# master_taylor.net
KiCad netlist of a schematic drawn in EAGLE
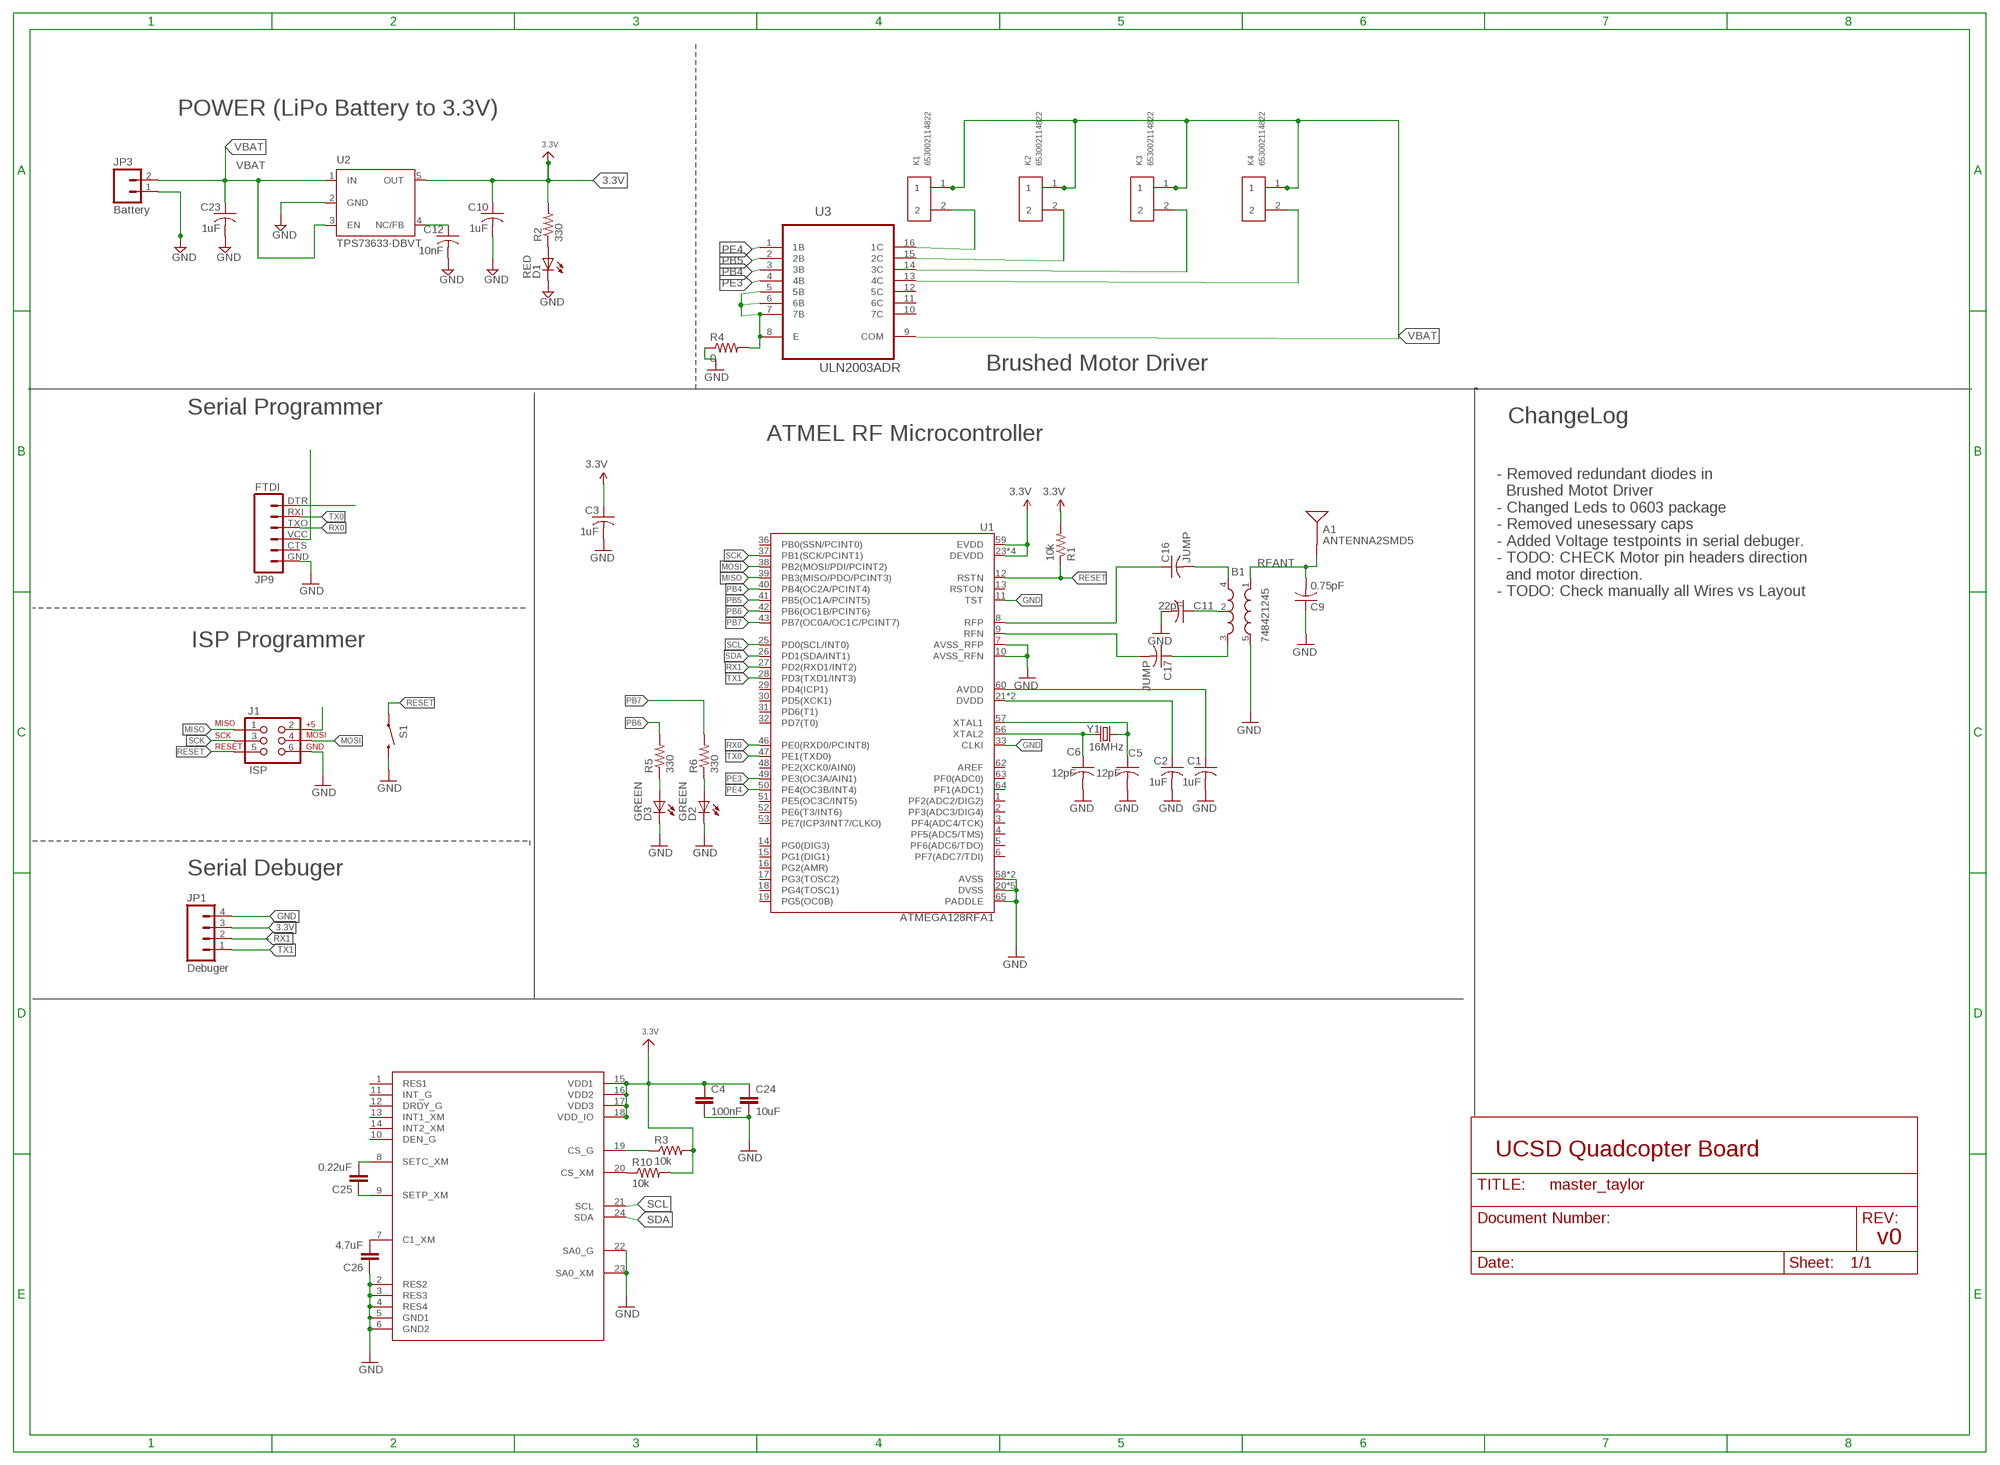
[diagram p0: schematic, sheet 1]

(export (version "E")
  (design (tool "Eeschema 10.0.6"))
  (components
    (comp (ref "A1")
      (value "ANTENNA2SMD5")
      (footprint "eagle-import:ANTENNA-CHIP5")
      (libsource (lib "eagle-import") (part "ANTENNA2SMD5"))
    )
    (comp (ref "B1")
      (value "748421245")
      (footprint "eagle-import:BALUN")
      (libsource (lib "eagle-import") (part "BALUN0805"))
    )
    (comp (ref "C1")
      (value "1uF")
      (footprint "eagle-import:C0805")
      (libsource (lib "eagle-import") (part "C-USC0805"))
    )
    (comp (ref "C2")
      (value "1uF")
      (footprint "eagle-import:C0805")
      (libsource (lib "eagle-import") (part "C-USC0805"))
    )
    (comp (ref "C3")
      (value "1uF")
      (footprint "eagle-import:C0805")
      (libsource (lib "eagle-import") (part "C-USC0805"))
    )
    (comp (ref "C4")
      (value "100nF")
      (footprint "eagle-import:0805")
      (libsource (lib "eagle-import") (part "CAP0805"))
    )
    (comp (ref "C5")
      (value "12pF")
      (footprint "eagle-import:C0805")
      (libsource (lib "eagle-import") (part "C-USC0805"))
    )
    (comp (ref "C6")
      (value "12pF")
      (footprint "eagle-import:C0805")
      (libsource (lib "eagle-import") (part "C-USC0805"))
    )
    (comp (ref "C9")
      (value "0.75pF")
      (footprint "eagle-import:C0805")
      (libsource (lib "eagle-import") (part "C-USC0805"))
    )
    (comp (ref "C10")
      (value "1uF")
      (footprint "eagle-import:C0805")
      (libsource (lib "eagle-import") (part "C-USC0805"))
    )
    (comp (ref "C11")
      (value "22pF")
      (footprint "eagle-import:C0805")
      (libsource (lib "eagle-import") (part "C-USC0805"))
    )
    (comp (ref "C12")
      (value "10nF")
      (footprint "eagle-import:C0805")
      (libsource (lib "eagle-import") (part "C-USC0805"))
    )
    (comp (ref "C16")
      (value "JUMP")
      (footprint "eagle-import:C0805")
      (libsource (lib "eagle-import") (part "C-USC0805"))
    )
    (comp (ref "C17")
      (value "JUMP")
      (footprint "eagle-import:C0805")
      (libsource (lib "eagle-import") (part "C-USC0805"))
    )
    (comp (ref "C23")
      (value "1uF")
      (footprint "eagle-import:C0805")
      (libsource (lib "eagle-import") (part "C-USC0805"))
    )
    (comp (ref "C24")
      (value "10uF")
      (footprint "eagle-import:0805")
      (libsource (lib "eagle-import") (part "CAP0805"))
    )
    (comp (ref "C25")
      (value "0.22uF")
      (footprint "eagle-import:0805")
      (libsource (lib "eagle-import") (part "CAP0805"))
    )
    (comp (ref "C26")
      (value "4.7uF")
      (footprint "eagle-import:0805")
      (libsource (lib "eagle-import") (part "CAP0805"))
    )
    (comp (ref "D1")
      (value "RED")
      (footprint "eagle-import:CHIPLED_0603")
      (libsource (lib "eagle-import") (part "LEDCHIPLED_0603"))
    )
    (comp (ref "D2")
      (value "GREEN")
      (footprint "eagle-import:CHIPLED_0603")
      (libsource (lib "eagle-import") (part "LEDCHIPLED_0603"))
    )
    (comp (ref "D3")
      (value "GREEN")
      (footprint "eagle-import:CHIPLED_0603")
      (libsource (lib "eagle-import") (part "LEDCHIPLED_0603"))
    )
    (comp (ref "J1")
      (value "ISP")
      (footprint "eagle-import:2X3-NS")
      (libsource (lib "eagle-import") (part "AVR_SPI_PRG_6NS"))
    )
    (comp (ref "JP1")
      (value "Debuger")
      (footprint "eagle-import:1X04")
      (libsource (lib "eagle-import") (part "M04PTH"))
    )
    (comp (ref "JP3")
      (value "Battery")
      (footprint "eagle-import:1X02")
      (libsource (lib "eagle-import") (part "M02PTH"))
    )
    (comp (ref "JP9")
      (value "FTDI")
      (footprint "eagle-import:FTDI_BASIC")
      (libsource (lib "eagle-import") (part "FTDI_BASICPTH"))
    )
    (comp (ref "K1")
      (value "653002114822")
      (footprint "eagle-import:653002114822")
      (libsource (lib "eagle-import") (part "653002114822"))
    )
    (comp (ref "K2")
      (value "653002114822")
      (footprint "eagle-import:653002114822")
      (libsource (lib "eagle-import") (part "653002114822"))
    )
    (comp (ref "K3")
      (value "653002114822")
      (footprint "eagle-import:653002114822")
      (libsource (lib "eagle-import") (part "653002114822"))
    )
    (comp (ref "K4")
      (value "653002114822")
      (footprint "eagle-import:653002114822")
      (libsource (lib "eagle-import") (part "653002114822"))
    )
    (comp (ref "R1")
      (value "10k")
      (footprint "eagle-import:R0805")
      (libsource (lib "eagle-import") (part "R-US_R0805"))
    )
    (comp (ref "R2")
      (value "330")
      (footprint "eagle-import:R0805")
      (libsource (lib "eagle-import") (part "R-US_R0805"))
    )
    (comp (ref "R3")
      (value "10k")
      (footprint "eagle-import:0805")
      (libsource (lib "eagle-import") (part "RESISTOR0805-RES"))
    )
    (comp (ref "R4")
      (value "0")
      (footprint "eagle-import:0805")
      (libsource (lib "eagle-import") (part "RESISTOR0805-RES"))
    )
    (comp (ref "R5")
      (value "330")
      (footprint "eagle-import:R0805")
      (libsource (lib "eagle-import") (part "R-US_R0805"))
    )
    (comp (ref "R6")
      (value "330")
      (footprint "eagle-import:R0805")
      (libsource (lib "eagle-import") (part "R-US_R0805"))
    )
    (comp (ref "R10")
      (value "10k")
      (footprint "eagle-import:0805")
      (libsource (lib "eagle-import") (part "RESISTOR0805-RES"))
    )
    (comp (ref "S1")
      (value "SWITCH-MOMENTARY-2SMD")
      (footprint "eagle-import:TACTILE_SWITCH_SMD")
      (libsource (lib "eagle-import") (part "SWITCH-MOMENTARY-2SMD"))
    )
    (comp (ref "U$1")
      (value "LSM9DS0")
      (footprint "eagle-import:LGA-24")
      (libsource (lib "eagle-import") (part "LSM9DS0"))
    )
    (comp (ref "U1")
      (value "ATMEGA128RFA1")
      (footprint "eagle-import:QFN-64")
      (libsource (lib "eagle-import") (part "ATMEGA128RFA1"))
    )
    (comp (ref "U2")
      (value "TPS73633-DBVT")
      (footprint "eagle-import:SOT23-DBV")
      (libsource (lib "eagle-import") (part "TPS73633-DBVT"))
    )
    (comp (ref "U3")
      (value "ULN2003ADR")
      (footprint "eagle-import:SOIC127P600X175-16N")
      (libsource (lib "eagle-import") (part "ULN2003ADR"))
    )
    (comp (ref "Y1")
      (value "16MHz")
      (footprint "eagle-import:CRYSTAL-SMD-5X3")
      (libsource (lib "eagle-import") (part "CRYSTAL5X3"))
    )
  )
  (nets
    (net (code "1") (name "/RFANT") (class "Default")
      (node (ref "A1") (pin "FEED") (pinfunction "SIGNAL_FEED") (pintype "bidirectional"))
      (node (ref "B1") (pin "1") (pinfunction "IN_1") (pintype "bidirectional"))
      (node (ref "C9") (pin "2") (pinfunction "2_2") (pintype "passive"))
    )
    (net (code "2") (name "3.3V") (class "Default")
      (node (ref "C10") (pin "1") (pinfunction "1_1") (pintype "passive"))
      (node (ref "C24") (pin "1") (pinfunction "1_1") (pintype "passive"))
      (node (ref "C3") (pin "1") (pinfunction "1_1") (pintype "passive"))
      (node (ref "C4") (pin "1") (pinfunction "1_1") (pintype "passive"))
      (node (ref "JP1") (pin "3") (pinfunction "3_3") (pintype "passive"))
      (node (ref "R1") (pin "2") (pinfunction "2_2") (pintype "passive"))
      (node (ref "R10") (pin "2") (pinfunction "2_2") (pintype "passive"))
      (node (ref "R2") (pin "2") (pinfunction "2_2") (pintype "passive"))
      (node (ref "R3") (pin "2") (pinfunction "2_2") (pintype "passive"))
      (node (ref "U$1") (pin "15") (pinfunction "VDD1_15") (pintype "bidirectional"))
      (node (ref "U$1") (pin "16") (pinfunction "VDD2_16") (pintype "bidirectional"))
      (node (ref "U$1") (pin "17") (pinfunction "VDD3_17") (pintype "bidirectional"))
      (node (ref "U$1") (pin "18") (pinfunction "VDD_IO_18") (pintype "bidirectional"))
      (node (ref "U1") (pin "23") (pinfunction "DEVDD_23") (pintype "bidirectional"))
      (node (ref "U1") (pin "34") (pinfunction "DEVDD_34") (pintype "bidirectional"))
      (node (ref "U1") (pin "44") (pinfunction "DEVDD_44") (pintype "bidirectional"))
      (node (ref "U1") (pin "54") (pinfunction "DEVDD_54") (pintype "bidirectional"))
      (node (ref "U1") (pin "59") (pinfunction "EVDD_59") (pintype "bidirectional"))
      (node (ref "U2") (pin "5") (pinfunction "OUT_5") (pintype "passive"))
    )
    (net (code "3") (name "GND") (class "Default")
      (node (ref "B1") (pin "5") (pinfunction "GND_5") (pintype "bidirectional"))
      (node (ref "C1") (pin "2") (pinfunction "2_2") (pintype "passive"))
      (node (ref "C10") (pin "2") (pinfunction "2_2") (pintype "passive"))
      (node (ref "C11") (pin "2") (pinfunction "2_2") (pintype "passive"))
      (node (ref "C12") (pin "2") (pinfunction "2_2") (pintype "passive"))
      (node (ref "C2") (pin "2") (pinfunction "2_2") (pintype "passive"))
      (node (ref "C23") (pin "2") (pinfunction "2_2") (pintype "passive"))
      (node (ref "C24") (pin "2") (pinfunction "2_2") (pintype "passive"))
      (node (ref "C26") (pin "1") (pinfunction "1_1") (pintype "passive"))
      (node (ref "C3") (pin "2") (pinfunction "2_2") (pintype "passive"))
      (node (ref "C4") (pin "2") (pinfunction "2_2") (pintype "passive"))
      (node (ref "C5") (pin "2") (pinfunction "2_2") (pintype "passive"))
      (node (ref "C6") (pin "2") (pinfunction "2_2") (pintype "passive"))
      (node (ref "C9") (pin "1") (pinfunction "1_1") (pintype "passive"))
      (node (ref "D1") (pin "C") (pinfunction "C_C") (pintype "passive"))
      (node (ref "D2") (pin "C") (pinfunction "C_C") (pintype "passive"))
      (node (ref "D3") (pin "C") (pinfunction "C_C") (pintype "passive"))
      (node (ref "J1") (pin "6") (pinfunction "6_6") (pintype "passive"))
      (node (ref "JP1") (pin "4") (pinfunction "4_4") (pintype "passive"))
      (node (ref "JP3") (pin "1") (pinfunction "1_1") (pintype "passive"))
      (node (ref "JP9") (pin "GND") (pinfunction "6_GND") (pintype "passive"))
      (node (ref "R4") (pin "1") (pinfunction "1_1") (pintype "passive"))
      (node (ref "S1") (pin "3") (pinfunction "2_3") (pintype "passive"))
      (node (ref "U$1") (pin "2") (pinfunction "RES2_2") (pintype "bidirectional"))
      (node (ref "U$1") (pin "22") (pinfunction "SA0_G_22") (pintype "bidirectional"))
      (node (ref "U$1") (pin "23") (pinfunction "SA0_XM_23") (pintype "bidirectional"))
      (node (ref "U$1") (pin "3") (pinfunction "RES3_3") (pintype "bidirectional"))
      (node (ref "U$1") (pin "4") (pinfunction "RES4_4") (pintype "bidirectional"))
      (node (ref "U$1") (pin "5") (pinfunction "GND1_5") (pintype "bidirectional"))
      (node (ref "U$1") (pin "6") (pinfunction "GND2_6") (pintype "bidirectional"))
      (node (ref "U1") (pin "10") (pinfunction "AVSS_RFN_10") (pintype "bidirectional"))
      (node (ref "U1") (pin "11") (pinfunction "TST_11") (pintype "bidirectional"))
      (node (ref "U1") (pin "20") (pinfunction "DVSS_20") (pintype "bidirectional"))
      (node (ref "U1") (pin "24") (pinfunction "DVSS_24") (pintype "bidirectional"))
      (node (ref "U1") (pin "33") (pinfunction "CLKI_33") (pintype "bidirectional"))
      (node (ref "U1") (pin "35") (pinfunction "DVSS_35") (pintype "bidirectional"))
      (node (ref "U1") (pin "45") (pinfunction "DVSS_45") (pintype "bidirectional"))
      (node (ref "U1") (pin "55") (pinfunction "DVSS_55") (pintype "bidirectional"))
      (node (ref "U1") (pin "58") (pinfunction "AVSS_58") (pintype "bidirectional"))
      (node (ref "U1") (pin "61") (pinfunction "AVSS_61") (pintype "bidirectional"))
      (node (ref "U1") (pin "65") (pinfunction "PADDLE_65") (pintype "bidirectional"))
      (node (ref "U1") (pin "7") (pinfunction "AVSS_RFP_7") (pintype "bidirectional"))
      (node (ref "U2") (pin "2") (pinfunction "GND_2") (pintype "input"))
    )
    (net (code "4") (name "MISO") (class "Default")
      (node (ref "J1") (pin "1") (pinfunction "1_1") (pintype "passive"))
      (node (ref "U1") (pin "39") (pinfunction "PB3(MISO/PDO/PCINT3)_39") (pintype "bidirectional"))
    )
    (net (code "5") (name "MOSI") (class "Default")
      (node (ref "J1") (pin "4") (pinfunction "4_4") (pintype "passive"))
      (node (ref "U1") (pin "38") (pinfunction "PB2(MOSI/PDI/PCINT2)_38") (pintype "bidirectional"))
    )
    (net (code "6") (name "Net-(B1-GND-Pad2)") (class "Default")
      (node (ref "B1") (pin "2") (pinfunction "GND_2") (pintype "bidirectional"))
      (node (ref "C11") (pin "1") (pinfunction "1_1") (pintype "passive"))
    )
    (net (code "7") (name "Net-(B1-OUT1)") (class "Default")
      (node (ref "B1") (pin "4") (pinfunction "OUT1_4") (pintype "bidirectional"))
      (node (ref "C16") (pin "2") (pinfunction "2_2") (pintype "passive"))
    )
    (net (code "8") (name "Net-(B1-OUT2)") (class "Default")
      (node (ref "B1") (pin "3") (pinfunction "OUT2_3") (pintype "bidirectional"))
      (node (ref "C17") (pin "1") (pinfunction "1_1") (pintype "passive"))
    )
    (net (code "9") (name "Net-(C2-Pad1)") (class "Default")
      (node (ref "C2") (pin "1") (pinfunction "1_1") (pintype "passive"))
      (node (ref "U1") (pin "21") (pinfunction "DVDD_21") (pintype "bidirectional"))
      (node (ref "U1") (pin "22") (pinfunction "DVDD_22") (pintype "bidirectional"))
    )
    (net (code "10") (name "Net-(D1-PadA)") (class "Default")
      (node (ref "D1") (pin "A") (pinfunction "A_A") (pintype "passive"))
      (node (ref "R2") (pin "1") (pinfunction "1_1") (pintype "passive"))
    )
    (net (code "11") (name "Net-(D2-PadA)") (class "Default")
      (node (ref "D2") (pin "A") (pinfunction "A_A") (pintype "passive"))
      (node (ref "R6") (pin "1") (pinfunction "1_1") (pintype "passive"))
    )
    (net (code "12") (name "Net-(D3-PadA)") (class "Default")
      (node (ref "D3") (pin "A") (pinfunction "A_A") (pintype "passive"))
      (node (ref "R5") (pin "1") (pinfunction "1_1") (pintype "passive"))
    )
    (net (code "13") (name "Net-(U$1-C1_XM)") (class "Default")
      (node (ref "C26") (pin "2") (pinfunction "2_2") (pintype "passive"))
      (node (ref "U$1") (pin "7") (pinfunction "C1_XM_7") (pintype "bidirectional"))
    )
    (net (code "14") (name "Net-(U$1-CS_G)") (class "Default")
      (node (ref "R3") (pin "1") (pinfunction "1_1") (pintype "passive"))
      (node (ref "U$1") (pin "19") (pinfunction "CS_G_19") (pintype "bidirectional"))
    )
    (net (code "15") (name "Net-(U$1-CS_XM)") (class "Default")
      (node (ref "R10") (pin "1") (pinfunction "1_1") (pintype "passive"))
      (node (ref "U$1") (pin "20") (pinfunction "CS_XM_20") (pintype "bidirectional"))
    )
    (net (code "16") (name "Net-(U$1-SETC_XM)") (class "Default")
      (node (ref "C25") (pin "2") (pinfunction "2_2") (pintype "passive"))
      (node (ref "U$1") (pin "8") (pinfunction "SETC_XM_8") (pintype "bidirectional"))
    )
    (net (code "17") (name "Net-(U$1-SETP_XM)") (class "Default")
      (node (ref "C25") (pin "1") (pinfunction "1_1") (pintype "passive"))
      (node (ref "U$1") (pin "9") (pinfunction "SETP_XM_9") (pintype "bidirectional"))
    )
    (net (code "18") (name "Net-(U1-AVDD)") (class "Default")
      (node (ref "C1") (pin "1") (pinfunction "1_1") (pintype "passive"))
      (node (ref "U1") (pin "60") (pinfunction "AVDD_60") (pintype "bidirectional"))
    )
    (net (code "19") (name "Net-(U1-RFN)") (class "Default")
      (node (ref "C17") (pin "2") (pinfunction "2_2") (pintype "passive"))
      (node (ref "U1") (pin "9") (pinfunction "RFN_9") (pintype "bidirectional"))
    )
    (net (code "20") (name "Net-(U1-RFP)") (class "Default")
      (node (ref "C16") (pin "1") (pinfunction "1_1") (pintype "passive"))
      (node (ref "U1") (pin "8") (pinfunction "RFP_8") (pintype "bidirectional"))
    )
    (net (code "21") (name "Net-(U1-XTAL1)") (class "Default")
      (node (ref "C5") (pin "1") (pinfunction "1_1") (pintype "passive"))
      (node (ref "U1") (pin "57") (pinfunction "XTAL1_57") (pintype "bidirectional"))
      (node (ref "Y1") (pin "3") (pinfunction "2_3") (pintype "passive"))
    )
    (net (code "22") (name "Net-(U1-XTAL2)") (class "Default")
      (node (ref "C6") (pin "1") (pinfunction "1_1") (pintype "passive"))
      (node (ref "U1") (pin "56") (pinfunction "XTAL2_56") (pintype "bidirectional"))
      (node (ref "Y1") (pin "1") (pinfunction "1_1") (pintype "passive"))
    )
    (net (code "23") (name "Net-(U2-NC{slash}FB)") (class "Default")
      (node (ref "C12") (pin "1") (pinfunction "1_1") (pintype "passive"))
      (node (ref "U2") (pin "4") (pinfunction "NC/FB_4") (pintype "passive"))
    )
    (net (code "24") (name "Net-(U3-1C)") (class "Default")
      (node (ref "K1") (pin "2") (pinfunction "2_2") (pintype "bidirectional"))
      (node (ref "U3") (pin "16") (pinfunction "1C_16") (pintype "output"))
    )
    (net (code "25") (name "Net-(U3-2C)") (class "Default")
      (node (ref "K2") (pin "2") (pinfunction "2_2") (pintype "bidirectional"))
      (node (ref "U3") (pin "15") (pinfunction "2C_15") (pintype "output"))
    )
    (net (code "26") (name "Net-(U3-3C)") (class "Default")
      (node (ref "K3") (pin "2") (pinfunction "2_2") (pintype "bidirectional"))
      (node (ref "U3") (pin "14") (pinfunction "3C_14") (pintype "output"))
    )
    (net (code "27") (name "Net-(U3-4C)") (class "Default")
      (node (ref "K4") (pin "2") (pinfunction "2_2") (pintype "bidirectional"))
      (node (ref "U3") (pin "13") (pinfunction "4C_13") (pintype "output"))
    )
    (net (code "28") (name "Net-(U3-5B)") (class "Default")
      (node (ref "R4") (pin "2") (pinfunction "2_2") (pintype "passive"))
      (node (ref "U3") (pin "5") (pinfunction "5B_5") (pintype "input"))
      (node (ref "U3") (pin "6") (pinfunction "6B_6") (pintype "input"))
      (node (ref "U3") (pin "7") (pinfunction "7B_7") (pintype "input"))
      (node (ref "U3") (pin "8") (pinfunction "E_8") (pintype "input"))
    )
    (net (code "29") (name "PB4") (class "Default")
      (node (ref "U1") (pin "40") (pinfunction "PB4(OC2A/PCINT4)_40") (pintype "bidirectional"))
      (node (ref "U3") (pin "3") (pinfunction "3B_3") (pintype "input"))
    )
    (net (code "30") (name "PB5") (class "Default")
      (node (ref "U1") (pin "41") (pinfunction "PB5(OC1A/PCINT5)_41") (pintype "bidirectional"))
      (node (ref "U3") (pin "2") (pinfunction "2B_2") (pintype "input"))
    )
    (net (code "31") (name "PB6") (class "Default")
      (node (ref "R5") (pin "2") (pinfunction "2_2") (pintype "passive"))
      (node (ref "U1") (pin "42") (pinfunction "PB6(OC1B/PCINT6)_42") (pintype "bidirectional"))
    )
    (net (code "32") (name "PB7") (class "Default")
      (node (ref "R6") (pin "2") (pinfunction "2_2") (pintype "passive"))
      (node (ref "U1") (pin "43") (pinfunction "PB7(OC0A/OC1C/PCINT7)_43") (pintype "bidirectional"))
    )
    (net (code "33") (name "PE3") (class "Default")
      (node (ref "U1") (pin "49") (pinfunction "PE3(OC3A/AIN1)_49") (pintype "bidirectional"))
      (node (ref "U3") (pin "4") (pinfunction "4B_4") (pintype "input"))
    )
    (net (code "34") (name "PE4") (class "Default")
      (node (ref "U1") (pin "50") (pinfunction "PE4(OC3B/INT4)_50") (pintype "bidirectional"))
      (node (ref "U3") (pin "1") (pinfunction "1B_1") (pintype "input"))
    )
    (net (code "35") (name "RESET") (class "Default")
      (node (ref "J1") (pin "5") (pinfunction "5_5") (pintype "passive"))
      (node (ref "R1") (pin "1") (pinfunction "1_1") (pintype "passive"))
      (node (ref "S1") (pin "1") (pinfunction "1_1") (pintype "passive"))
      (node (ref "U1") (pin "12") (pinfunction "RSTN_12") (pintype "bidirectional"))
    )
    (net (code "36") (name "RX0") (class "Default")
      (node (ref "JP9") (pin "TXO") (pinfunction "3_TXO") (pintype "passive"))
      (node (ref "U1") (pin "46") (pinfunction "PE0(RXD0/PCINT8)_46") (pintype "bidirectional"))
    )
    (net (code "37") (name "RX1") (class "Default")
      (node (ref "JP1") (pin "2") (pinfunction "2_2") (pintype "passive"))
      (node (ref "U1") (pin "27") (pinfunction "PD2(RXD1/INT2)_27") (pintype "bidirectional"))
    )
    (net (code "38") (name "SCK") (class "Default")
      (node (ref "J1") (pin "3") (pinfunction "3_3") (pintype "passive"))
      (node (ref "U1") (pin "37") (pinfunction "PB1(SCK/PCINT1)_37") (pintype "bidirectional"))
    )
    (net (code "39") (name "SCL") (class "Default")
      (node (ref "U$1") (pin "21") (pinfunction "SCL_21") (pintype "bidirectional"))
      (node (ref "U1") (pin "25") (pinfunction "PD0(SCL/INT0)_25") (pintype "bidirectional"))
    )
    (net (code "40") (name "SDA") (class "Default")
      (node (ref "U$1") (pin "24") (pinfunction "SDA_24") (pintype "bidirectional"))
      (node (ref "U1") (pin "26") (pinfunction "PD1(SDA/INT1)_26") (pintype "bidirectional"))
    )
    (net (code "41") (name "TX0") (class "Default")
      (node (ref "JP9") (pin "RXI") (pinfunction "2_RXI") (pintype "passive"))
      (node (ref "U1") (pin "47") (pinfunction "PE1(TXD0)_47") (pintype "bidirectional"))
    )
    (net (code "42") (name "TX1") (class "Default")
      (node (ref "JP1") (pin "1") (pinfunction "1_1") (pintype "passive"))
      (node (ref "U1") (pin "28") (pinfunction "PD3(TXD1/INT3)_28") (pintype "bidirectional"))
    )
    (net (code "43") (name "VBAT") (class "Default")
      (node (ref "C23") (pin "1") (pinfunction "1_1") (pintype "passive"))
      (node (ref "JP3") (pin "2") (pinfunction "2_2") (pintype "passive"))
      (node (ref "K1") (pin "1") (pinfunction "1_1") (pintype "bidirectional"))
      (node (ref "K2") (pin "1") (pinfunction "1_1") (pintype "bidirectional"))
      (node (ref "K3") (pin "1") (pinfunction "1_1") (pintype "bidirectional"))
      (node (ref "K4") (pin "1") (pinfunction "1_1") (pintype "bidirectional"))
      (node (ref "U2") (pin "1") (pinfunction "IN_1") (pintype "input"))
      (node (ref "U2") (pin "3") (pinfunction "EN_3") (pintype "power_in"))
      (node (ref "U3") (pin "9") (pinfunction "COM_9") (pintype "output"))
    )
    (net (code "44") (name "unconnected-(J1-Pad2)") (class "Default")
      (node (ref "J1") (pin "2") (pinfunction "2_2") (pintype "passive"))
    )
    (net (code "45") (name "unconnected-(JP9-1-PadDTR)") (class "Default")
      (node (ref "JP9") (pin "DTR") (pinfunction "1_DTR") (pintype "passive"))
    )
    (net (code "46") (name "unconnected-(JP9-4-PadVCC)") (class "Default")
      (node (ref "JP9") (pin "VCC") (pinfunction "4_VCC") (pintype "passive"))
    )
    (net (code "47") (name "unconnected-(JP9-5-PadCTS)") (class "Default")
      (node (ref "JP9") (pin "CTS") (pinfunction "5_CTS") (pintype "passive"))
    )
    (net (code "48") (name "unconnected-(U$1-DEN_G-Pad10)") (class "Default")
      (node (ref "U$1") (pin "10") (pinfunction "DEN_G_10") (pintype "bidirectional"))
    )
    (net (code "49") (name "unconnected-(U$1-DRDY_G-Pad12)") (class "Default")
      (node (ref "U$1") (pin "12") (pinfunction "DRDY_G_12") (pintype "bidirectional"))
    )
    (net (code "50") (name "unconnected-(U$1-INT1_XM-Pad13)") (class "Default")
      (node (ref "U$1") (pin "13") (pinfunction "INT1_XM_13") (pintype "bidirectional"))
    )
    (net (code "51") (name "unconnected-(U$1-INT2_XM-Pad14)") (class "Default")
      (node (ref "U$1") (pin "14") (pinfunction "INT2_XM_14") (pintype "bidirectional"))
    )
    (net (code "52") (name "unconnected-(U$1-INT_G-Pad11)") (class "Default")
      (node (ref "U$1") (pin "11") (pinfunction "INT_G_11") (pintype "bidirectional"))
    )
    (net (code "53") (name "unconnected-(U$1-RES1-Pad1)") (class "Default")
      (node (ref "U$1") (pin "1") (pinfunction "RES1_1") (pintype "bidirectional"))
    )
    (net (code "54") (name "unconnected-(U1-AREF-Pad62)") (class "Default")
      (node (ref "U1") (pin "62") (pinfunction "AREF_62") (pintype "bidirectional"))
    )
    (net (code "55") (name "unconnected-(U1-PB0(SSN{slash}PCINT0)-Pad36)") (class "Default")
      (node (ref "U1") (pin "36") (pinfunction "PB0(SSN/PCINT0)_36") (pintype "bidirectional"))
    )
    (net (code "56") (name "unconnected-(U1-PD4(ICP1)-Pad29)") (class "Default")
      (node (ref "U1") (pin "29") (pinfunction "PD4(ICP1)_29") (pintype "bidirectional"))
    )
    (net (code "57") (name "unconnected-(U1-PD5(XCK1)-Pad30)") (class "Default")
      (node (ref "U1") (pin "30") (pinfunction "PD5(XCK1)_30") (pintype "bidirectional"))
    )
    (net (code "58") (name "unconnected-(U1-PD6(T1)-Pad31)") (class "Default")
      (node (ref "U1") (pin "31") (pinfunction "PD6(T1)_31") (pintype "bidirectional"))
    )
    (net (code "59") (name "unconnected-(U1-PD7(T0)-Pad32)") (class "Default")
      (node (ref "U1") (pin "32") (pinfunction "PD7(T0)_32") (pintype "bidirectional"))
    )
    (net (code "60") (name "unconnected-(U1-PE2(XCK0{slash}AIN0)-Pad48)") (class "Default")
      (node (ref "U1") (pin "48") (pinfunction "PE2(XCK0/AIN0)_48") (pintype "bidirectional"))
    )
    (net (code "61") (name "unconnected-(U1-PE5(OC3C{slash}INT5)-Pad51)") (class "Default")
      (node (ref "U1") (pin "51") (pinfunction "PE5(OC3C/INT5)_51") (pintype "bidirectional"))
    )
    (net (code "62") (name "unconnected-(U1-PE6(T3{slash}INT6)-Pad52)") (class "Default")
      (node (ref "U1") (pin "52") (pinfunction "PE6(T3/INT6)_52") (pintype "bidirectional"))
    )
    (net (code "63") (name "unconnected-(U1-PE7(ICP3{slash}INT7{slash}CLKO)-Pad53)") (class "Default")
      (node (ref "U1") (pin "53") (pinfunction "PE7(ICP3/INT7/CLKO)_53") (pintype "bidirectional"))
    )
    (net (code "64") (name "unconnected-(U1-PF0(ADC0)-Pad63)") (class "Default")
      (node (ref "U1") (pin "63") (pinfunction "PF0(ADC0)_63") (pintype "bidirectional"))
    )
    (net (code "65") (name "unconnected-(U1-PF1(ADC1)-Pad64)") (class "Default")
      (node (ref "U1") (pin "64") (pinfunction "PF1(ADC1)_64") (pintype "bidirectional"))
    )
    (net (code "66") (name "unconnected-(U1-PF2(ADC2{slash}DIG2)-Pad1)") (class "Default")
      (node (ref "U1") (pin "1") (pinfunction "PF2(ADC2/DIG2)_1") (pintype "bidirectional"))
    )
    (net (code "67") (name "unconnected-(U1-PF3(ADC3{slash}DIG4)-Pad2)") (class "Default")
      (node (ref "U1") (pin "2") (pinfunction "PF3(ADC3/DIG4)_2") (pintype "bidirectional"))
    )
    (net (code "68") (name "unconnected-(U1-PF4(ADC4{slash}TCK)-Pad3)") (class "Default")
      (node (ref "U1") (pin "3") (pinfunction "PF4(ADC4/TCK)_3") (pintype "bidirectional"))
    )
    (net (code "69") (name "unconnected-(U1-PF5(ADC5{slash}TMS)-Pad4)") (class "Default")
      (node (ref "U1") (pin "4") (pinfunction "PF5(ADC5/TMS)_4") (pintype "bidirectional"))
    )
    (net (code "70") (name "unconnected-(U1-PF6(ADC6{slash}TDO)-Pad5)") (class "Default")
      (node (ref "U1") (pin "5") (pinfunction "PF6(ADC6/TDO)_5") (pintype "bidirectional"))
    )
    (net (code "71") (name "unconnected-(U1-PF7(ADC7{slash}TDI)-Pad6)") (class "Default")
      (node (ref "U1") (pin "6") (pinfunction "PF7(ADC7/TDI)_6") (pintype "bidirectional"))
    )
    (net (code "72") (name "unconnected-(U1-PG0(DIG3)-Pad14)") (class "Default")
      (node (ref "U1") (pin "14") (pinfunction "PG0(DIG3)_14") (pintype "bidirectional"))
    )
    (net (code "73") (name "unconnected-(U1-PG1(DIG1)-Pad15)") (class "Default")
      (node (ref "U1") (pin "15") (pinfunction "PG1(DIG1)_15") (pintype "bidirectional"))
    )
    (net (code "74") (name "unconnected-(U1-PG2(AMR)-Pad16)") (class "Default")
      (node (ref "U1") (pin "16") (pinfunction "PG2(AMR)_16") (pintype "bidirectional"))
    )
    (net (code "75") (name "unconnected-(U1-PG3(TOSC2)-Pad17)") (class "Default")
      (node (ref "U1") (pin "17") (pinfunction "PG3(TOSC2)_17") (pintype "bidirectional"))
    )
    (net (code "76") (name "unconnected-(U1-PG4(TOSC1)-Pad18)") (class "Default")
      (node (ref "U1") (pin "18") (pinfunction "PG4(TOSC1)_18") (pintype "bidirectional"))
    )
    (net (code "77") (name "unconnected-(U1-PG5(OC0B)-Pad19)") (class "Default")
      (node (ref "U1") (pin "19") (pinfunction "PG5(OC0B)_19") (pintype "bidirectional"))
    )
    (net (code "78") (name "unconnected-(U1-RSTON-Pad13)") (class "Default")
      (node (ref "U1") (pin "13") (pinfunction "RSTON_13") (pintype "bidirectional"))
    )
    (net (code "79") (name "unconnected-(U3-5C-Pad12)") (class "Default")
      (node (ref "U3") (pin "12") (pinfunction "5C_12") (pintype "output"))
    )
    (net (code "80") (name "unconnected-(U3-6C-Pad11)") (class "Default")
      (node (ref "U3") (pin "11") (pinfunction "6C_11") (pintype "output"))
    )
    (net (code "81") (name "unconnected-(U3-7C-Pad10)") (class "Default")
      (node (ref "U3") (pin "10") (pinfunction "7C_10") (pintype "output"))
    )
  )
)
